# koosh_power.net
KiCad netlist of a schematic drawn in Altium Designer
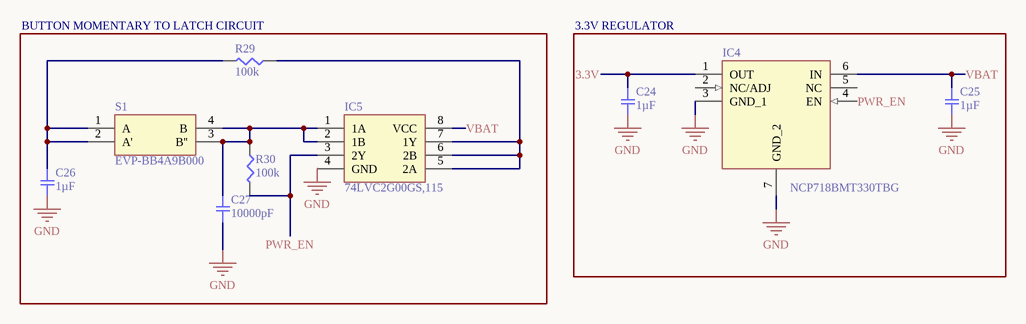
[diagram p0: koosh_power.SchDoc]

(export (version "E")
  (design (tool "Eeschema 10.0.6"))
  (components
    (comp (ref "C24")
      (value "1µF")
      (footprint "SMD-0402C")
      (description "CAP CER 1UF 10V X7S 0402")
      (fields
        (field (name "DIGI-KEY PART NUMBER") "490-13409-1-ND")
        (field (name "PART NUMBER") "GCM155C71A105KE38D")
      )
      (libsource (lib "capacitor_murata_0402") (part "GCM155C71A105KE38D"))
    )
    (comp (ref "C25")
      (value "1µF")
      (footprint "SMD-0402C")
      (description "CAP CER 1UF 10V X7S 0402")
      (fields
        (field (name "DIGI-KEY PART NUMBER") "490-13409-1-ND")
        (field (name "PART NUMBER") "GCM155C71A105KE38D")
      )
      (libsource (lib "capacitor_murata_0402") (part "GCM155C71A105KE38D"))
    )
    (comp (ref "C26")
      (value "1µF")
      (footprint "SMD-0402C")
      (description "CAP CER 1UF 10V X7S 0402")
      (fields
        (field (name "DIGI-KEY PART NUMBER") "490-13409-1-ND")
        (field (name "PART NUMBER") "GCM155C71A105KE38D")
      )
      (libsource (lib "capacitor_murata_0402") (part "GCM155C71A105KE38D"))
    )
    (comp (ref "C27")
      (value "10000pF")
      (footprint "SMD-0402C")
      (description "CAP CER 10000PF 50V X7R 0402")
      (fields
        (field (name "DIGI-KEY PART NUMBER") "490-4762-1-ND")
        (field (name "PART NUMBER") "GCM155R71H103KA55D")
      )
      (libsource (lib "capacitor_murata_0402") (part "GCM155R71H103KA55D"))
    )
    (comp (ref "IC4")
      (value "NCP718BMT330TBG")
      (footprint "SamacSys:SON65P200X200X80-7N")
      (description "Integrated Circuit")
      (fields
        (field (name "MOUSER PART NUMBER") "863-NCP718BMT330TBG")
        (field (name "RS PART NUMBER") "1861278")
      )
      (libsource (lib "*") (part "NCP718BMT330TBG"))
    )
    (comp (ref "IC5")
      (value "74LVC2G00GS,115")
      (footprint "SamacSys:74AXP2T3407GSX")
      (description "Integrated Circuit")
      (libsource (lib "*") (part "74LVC2G00GS,115"))
    )
    (comp (ref "R29")
      (value "100k")
      (footprint "SMD-0402-RES")
      (description "RES SMD 100K OHM 5% 1/10W 0402")
      (fields (field (name "PART NUMBER") "ERJ-2GEJ104X") (field (name "DIGI-KEY PART NUMBER") "P100KJCT-ND"))
      (libsource (lib "Panasonic_ERJ_0402") (part "ERJ-2GEJ104X"))
    )
    (comp (ref "R30")
      (value "100k")
      (footprint "SMD-0402-RES")
      (description "RES SMD 100K OHM 5% 1/10W 0402")
      (fields (field (name "PART NUMBER") "ERJ-2GEJ104X") (field (name "DIGI-KEY PART NUMBER") "P100KJCT-ND"))
      (libsource (lib "Panasonic_ERJ_0402") (part "ERJ-2GEJ104X"))
    )
    (comp (ref "S1")
      (value "EVP-BB4A9B000")
      (footprint "SamacSys:EVPBB2A9B000")
      (description "Switch")
      (fields (field (name "MOUSER PART NUMBER") "667-EVP-BB4A9B000"))
      (libsource (lib "*") (part "EVP-BB4A9B000"))
    )
  )
  (nets
    (net (code "1") (name "/3.3V") (class "Default")
      (node (ref "C24") (pin "1") (pinfunction "1_1") (pintype "passive"))
      (node (ref "IC4") (pin "1") (pinfunction "OUT_1") (pintype "power_in"))
    )
    (net (code "2") (name "/PWR_EN") (class "Default")
      (node (ref "IC4") (pin "4") (pinfunction "EN_4") (pintype "input"))
      (node (ref "IC5") (pin "3") (pinfunction "2Y_3") (pintype "passive"))
      (node (ref "R30") (pin "2") (pinfunction "2_2") (pintype "passive"))
    )
    (net (code "3") (name "/VBAT") (class "Default")
      (node (ref "C25") (pin "1") (pinfunction "1_1") (pintype "passive"))
      (node (ref "IC4") (pin "6") (pinfunction "IN_6") (pintype "power_in"))
      (node (ref "IC5") (pin "8") (pinfunction "VCC_8") (pintype "passive"))
    )
    (net (code "4") (name "GND") (class "Default")
      (node (ref "C24") (pin "2") (pinfunction "2_2") (pintype "passive"))
      (node (ref "C25") (pin "2") (pinfunction "2_2") (pintype "passive"))
      (node (ref "C26") (pin "2") (pinfunction "2_2") (pintype "passive"))
      (node (ref "C27") (pin "1") (pinfunction "1_1") (pintype "passive"))
      (node (ref "IC4") (pin "3") (pinfunction "GND_1_3") (pintype "power_in"))
      (node (ref "IC4") (pin "7") (pinfunction "GND_2_7") (pintype "power_in"))
      (node (ref "IC5") (pin "4") (pinfunction "GND_4") (pintype "passive"))
    )
    (net (code "5") (name "Net-(IC5-1A)") (class "Default")
      (node (ref "C27") (pin "2") (pinfunction "2_2") (pintype "passive"))
      (node (ref "IC5") (pin "1") (pinfunction "1A_1") (pintype "passive"))
      (node (ref "IC5") (pin "2") (pinfunction "1B_2") (pintype "passive"))
      (node (ref "R30") (pin "1") (pinfunction "1_1") (pintype "passive"))
      (node (ref "S1") (pin "3") (pinfunction "B''_3") (pintype "passive"))
      (node (ref "S1") (pin "4") (pinfunction "B_4") (pintype "passive"))
    )
    (net (code "6") (name "Net-(IC5-1Y)") (class "Default")
      (node (ref "IC5") (pin "5") (pinfunction "2A_5") (pintype "passive"))
      (node (ref "IC5") (pin "6") (pinfunction "2B_6") (pintype "passive"))
      (node (ref "IC5") (pin "7") (pinfunction "1Y_7") (pintype "passive"))
      (node (ref "R29") (pin "1") (pinfunction "1_1") (pintype "passive"))
    )
    (net (code "7") (name "Net-(S1-A')") (class "Default")
      (node (ref "C26") (pin "1") (pinfunction "1_1") (pintype "passive"))
      (node (ref "R29") (pin "2") (pinfunction "2_2") (pintype "passive"))
      (node (ref "S1") (pin "1") (pinfunction "A_1") (pintype "passive"))
      (node (ref "S1") (pin "2") (pinfunction "A'_2") (pintype "passive"))
    )
    (net (code "8") (name "unconnected-(IC4-NC-Pad5)") (class "Default")
      (node (ref "IC4") (pin "5") (pinfunction "NC_5") (pintype "passive"))
    )
    (net (code "9") (name "unconnected-(IC4-NC{slash}ADJ-Pad2)") (class "Default")
      (node (ref "IC4") (pin "2") (pinfunction "NC/ADJ_2") (pintype "input"))
    )
  )
)
